# KeyInput_ABH.net
KiCad netlist of a schematic drawn in Altium Designer
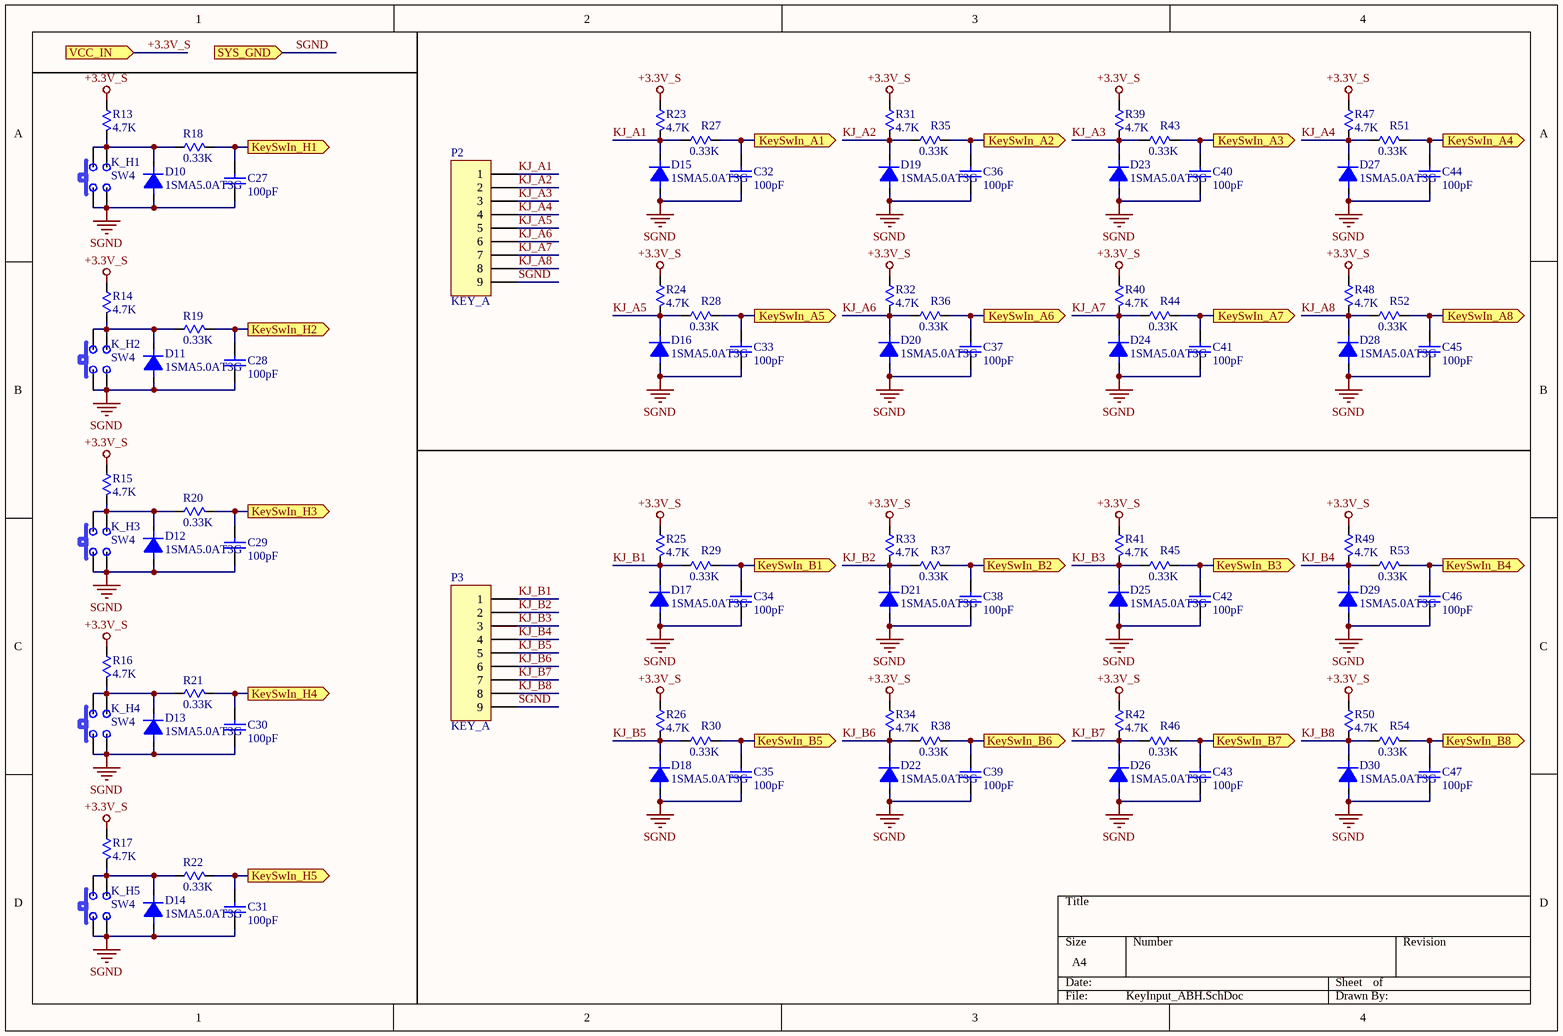
[diagram p0: KeyInput_ABH.SchDoc]

(export (version "E")
  (design (tool "Eeschema 10.0.6"))
  (components
    (comp (ref "C27")
      (value "100pF")
      (footprint "C0805")
      (description "Capacitor")
      (fields (field (name "PUBLISHER") "Altium Limited"))
      (libsource (lib "Miscellaneous Devices") (part "Cap"))
    )
    (comp (ref "C28")
      (value "100pF")
      (footprint "C0805")
      (description "Capacitor")
      (fields (field (name "PUBLISHER") "Altium Limited"))
      (libsource (lib "Miscellaneous Devices") (part "Cap"))
    )
    (comp (ref "C29")
      (value "100pF")
      (footprint "C0805")
      (description "Capacitor")
      (fields (field (name "PUBLISHER") "Altium Limited"))
      (libsource (lib "Miscellaneous Devices") (part "Cap"))
    )
    (comp (ref "C30")
      (value "100pF")
      (footprint "C0805")
      (description "Capacitor")
      (fields (field (name "PUBLISHER") "Altium Limited"))
      (libsource (lib "Miscellaneous Devices") (part "Cap"))
    )
    (comp (ref "C31")
      (value "100pF")
      (footprint "C0805")
      (description "Capacitor")
      (fields (field (name "PUBLISHER") "Altium Limited"))
      (libsource (lib "Miscellaneous Devices") (part "Cap"))
    )
    (comp (ref "C32")
      (value "100pF")
      (footprint "C0805")
      (description "Capacitor")
      (fields (field (name "PUBLISHER") "Altium Limited"))
      (libsource (lib "Miscellaneous Devices") (part "Cap"))
    )
    (comp (ref "C33")
      (value "100pF")
      (footprint "C0805")
      (description "Capacitor")
      (fields (field (name "PUBLISHER") "Altium Limited"))
      (libsource (lib "Miscellaneous Devices") (part "Cap"))
    )
    (comp (ref "C34")
      (value "100pF")
      (footprint "C0805")
      (description "Capacitor")
      (fields (field (name "PUBLISHER") "Altium Limited"))
      (libsource (lib "Miscellaneous Devices") (part "Cap"))
    )
    (comp (ref "C35")
      (value "100pF")
      (footprint "C0805")
      (description "Capacitor")
      (fields (field (name "PUBLISHER") "Altium Limited"))
      (libsource (lib "Miscellaneous Devices") (part "Cap"))
    )
    (comp (ref "C36")
      (value "100pF")
      (footprint "C0805")
      (description "Capacitor")
      (fields (field (name "PUBLISHER") "Altium Limited"))
      (libsource (lib "Miscellaneous Devices") (part "Cap"))
    )
    (comp (ref "C37")
      (value "100pF")
      (footprint "C0805")
      (description "Capacitor")
      (fields (field (name "PUBLISHER") "Altium Limited"))
      (libsource (lib "Miscellaneous Devices") (part "Cap"))
    )
    (comp (ref "C38")
      (value "100pF")
      (footprint "C0805")
      (description "Capacitor")
      (fields (field (name "PUBLISHER") "Altium Limited"))
      (libsource (lib "Miscellaneous Devices") (part "Cap"))
    )
    (comp (ref "C39")
      (value "100pF")
      (footprint "C0805")
      (description "Capacitor")
      (fields (field (name "PUBLISHER") "Altium Limited"))
      (libsource (lib "Miscellaneous Devices") (part "Cap"))
    )
    (comp (ref "C40")
      (value "100pF")
      (footprint "C0805")
      (description "Capacitor")
      (fields (field (name "PUBLISHER") "Altium Limited"))
      (libsource (lib "Miscellaneous Devices") (part "Cap"))
    )
    (comp (ref "C41")
      (value "100pF")
      (footprint "C0805")
      (description "Capacitor")
      (fields (field (name "PUBLISHER") "Altium Limited"))
      (libsource (lib "Miscellaneous Devices") (part "Cap"))
    )
    (comp (ref "C42")
      (value "100pF")
      (footprint "C0805")
      (description "Capacitor")
      (fields (field (name "PUBLISHER") "Altium Limited"))
      (libsource (lib "Miscellaneous Devices") (part "Cap"))
    )
    (comp (ref "C43")
      (value "100pF")
      (footprint "C0805")
      (description "Capacitor")
      (fields (field (name "PUBLISHER") "Altium Limited"))
      (libsource (lib "Miscellaneous Devices") (part "Cap"))
    )
    (comp (ref "C44")
      (value "100pF")
      (footprint "C0805")
      (description "Capacitor")
      (fields (field (name "PUBLISHER") "Altium Limited"))
      (libsource (lib "Miscellaneous Devices") (part "Cap"))
    )
    (comp (ref "C45")
      (value "100pF")
      (footprint "C0805")
      (description "Capacitor")
      (fields (field (name "PUBLISHER") "Altium Limited"))
      (libsource (lib "Miscellaneous Devices") (part "Cap"))
    )
    (comp (ref "C46")
      (value "100pF")
      (footprint "C0805")
      (description "Capacitor")
      (fields (field (name "PUBLISHER") "Altium Limited"))
      (libsource (lib "Miscellaneous Devices") (part "Cap"))
    )
    (comp (ref "C47")
      (value "100pF")
      (footprint "C0805")
      (description "Capacitor")
      (fields (field (name "PUBLISHER") "Altium Limited"))
      (libsource (lib "Miscellaneous Devices") (part "Cap"))
    )
    (comp (ref "D10")
      (value "1SMA5.0AT3G")
      (footprint "SMA")
      (description "Diode")
      (libsource (lib "*") (part "DIODE1"))
    )
    (comp (ref "D11")
      (value "1SMA5.0AT3G")
      (footprint "SMA")
      (description "Diode")
      (libsource (lib "*") (part "DIODE1"))
    )
    (comp (ref "D12")
      (value "1SMA5.0AT3G")
      (footprint "SMA")
      (description "Diode")
      (libsource (lib "*") (part "DIODE1"))
    )
    (comp (ref "D13")
      (value "1SMA5.0AT3G")
      (footprint "SMA")
      (description "Diode")
      (libsource (lib "*") (part "DIODE1"))
    )
    (comp (ref "D14")
      (value "1SMA5.0AT3G")
      (footprint "SMA")
      (description "Diode")
      (libsource (lib "*") (part "DIODE1"))
    )
    (comp (ref "D15")
      (value "1SMA5.0AT3G")
      (footprint "SMA")
      (description "Diode")
      (libsource (lib "*") (part "DIODE1"))
    )
    (comp (ref "D16")
      (value "1SMA5.0AT3G")
      (footprint "SMA")
      (description "Diode")
      (libsource (lib "*") (part "DIODE1"))
    )
    (comp (ref "D17")
      (value "1SMA5.0AT3G")
      (footprint "SMA")
      (description "Diode")
      (libsource (lib "*") (part "DIODE1"))
    )
    (comp (ref "D18")
      (value "1SMA5.0AT3G")
      (footprint "SMA")
      (description "Diode")
      (libsource (lib "*") (part "DIODE1"))
    )
    (comp (ref "D19")
      (value "1SMA5.0AT3G")
      (footprint "SMA")
      (description "Diode")
      (libsource (lib "*") (part "DIODE1"))
    )
    (comp (ref "D20")
      (value "1SMA5.0AT3G")
      (footprint "SMA")
      (description "Diode")
      (libsource (lib "*") (part "DIODE1"))
    )
    (comp (ref "D21")
      (value "1SMA5.0AT3G")
      (footprint "SMA")
      (description "Diode")
      (libsource (lib "*") (part "DIODE1"))
    )
    (comp (ref "D22")
      (value "1SMA5.0AT3G")
      (footprint "SMA")
      (description "Diode")
      (libsource (lib "*") (part "DIODE1"))
    )
    (comp (ref "D23")
      (value "1SMA5.0AT3G")
      (footprint "SMA")
      (description "Diode")
      (libsource (lib "*") (part "DIODE1"))
    )
    (comp (ref "D24")
      (value "1SMA5.0AT3G")
      (footprint "SMA")
      (description "Diode")
      (libsource (lib "*") (part "DIODE1"))
    )
    (comp (ref "D25")
      (value "1SMA5.0AT3G")
      (footprint "SMA")
      (description "Diode")
      (libsource (lib "*") (part "DIODE1"))
    )
    (comp (ref "D26")
      (value "1SMA5.0AT3G")
      (footprint "SMA")
      (description "Diode")
      (libsource (lib "*") (part "DIODE1"))
    )
    (comp (ref "D27")
      (value "1SMA5.0AT3G")
      (footprint "SMA")
      (description "Diode")
      (libsource (lib "*") (part "DIODE1"))
    )
    (comp (ref "D28")
      (value "1SMA5.0AT3G")
      (footprint "SMA")
      (description "Diode")
      (libsource (lib "*") (part "DIODE1"))
    )
    (comp (ref "D29")
      (value "1SMA5.0AT3G")
      (footprint "SMA")
      (description "Diode")
      (libsource (lib "*") (part "DIODE1"))
    )
    (comp (ref "D30")
      (value "1SMA5.0AT3G")
      (footprint "SMA")
      (description "Diode")
      (libsource (lib "*") (part "DIODE1"))
    )
    (comp (ref "K_H1")
      (value "SW4")
      (footprint "SW-MEC")
      (libsource (lib "Passive Components Class") (part "SW-key"))
    )
    (comp (ref "K_H2")
      (value "SW4")
      (footprint "SW-MEC")
      (libsource (lib "Passive Components Class") (part "SW-key"))
    )
    (comp (ref "K_H3")
      (value "SW4")
      (footprint "SW-MEC")
      (libsource (lib "Passive Components Class") (part "SW-key"))
    )
    (comp (ref "K_H4")
      (value "SW4")
      (footprint "SW-MEC")
      (libsource (lib "Passive Components Class") (part "SW-key"))
    )
    (comp (ref "K_H5")
      (value "SW4")
      (footprint "SW-MEC")
      (libsource (lib "Passive Components Class") (part "SW-key"))
    )
    (comp (ref "P2")
      (value "KEY_A")
      (footprint "HDR1X9")
      (description "Header, 9-Pin")
      (fields (field (name "PUBLISHER") "Altium Limited"))
      (libsource (lib "Miscellaneous Connectors") (part "Header 9"))
    )
    (comp (ref "P3")
      (value "KEY_A")
      (footprint "HDR1X9")
      (description "Header, 9-Pin")
      (fields (field (name "PUBLISHER") "Altium Limited"))
      (libsource (lib "Miscellaneous Connectors") (part "Header 9"))
    )
    (comp (ref "R13")
      (value "4.7K")
      (footprint "R0805")
      (description "Resistor")
      (fields (field (name "PUBLISHER") "Altium Limited"))
      (libsource (lib "Passive Components Class") (part "RES"))
    )
    (comp (ref "R14")
      (value "4.7K")
      (footprint "R0805")
      (description "Resistor")
      (fields (field (name "PUBLISHER") "Altium Limited"))
      (libsource (lib "Passive Components Class") (part "RES"))
    )
    (comp (ref "R15")
      (value "4.7K")
      (footprint "R0805")
      (description "Resistor")
      (fields (field (name "PUBLISHER") "Altium Limited"))
      (libsource (lib "Passive Components Class") (part "RES"))
    )
    (comp (ref "R16")
      (value "4.7K")
      (footprint "R0805")
      (description "Resistor")
      (fields (field (name "PUBLISHER") "Altium Limited"))
      (libsource (lib "Passive Components Class") (part "RES"))
    )
    (comp (ref "R17")
      (value "4.7K")
      (footprint "R0805")
      (description "Resistor")
      (fields (field (name "PUBLISHER") "Altium Limited"))
      (libsource (lib "Passive Components Class") (part "RES"))
    )
    (comp (ref "R18")
      (value "0.33K")
      (footprint "R0805")
      (description "Resistor")
      (fields (field (name "PUBLISHER") "Altium Limited"))
      (libsource (lib "Passive Components Class") (part "RES"))
    )
    (comp (ref "R19")
      (value "0.33K")
      (footprint "R0805")
      (description "Resistor")
      (fields (field (name "PUBLISHER") "Altium Limited"))
      (libsource (lib "Passive Components Class") (part "RES"))
    )
    (comp (ref "R20")
      (value "0.33K")
      (footprint "R0805")
      (description "Resistor")
      (fields (field (name "PUBLISHER") "Altium Limited"))
      (libsource (lib "Passive Components Class") (part "RES"))
    )
    (comp (ref "R21")
      (value "0.33K")
      (footprint "R0805")
      (description "Resistor")
      (fields (field (name "PUBLISHER") "Altium Limited"))
      (libsource (lib "Passive Components Class") (part "RES"))
    )
    (comp (ref "R22")
      (value "0.33K")
      (footprint "R0805")
      (description "Resistor")
      (fields (field (name "PUBLISHER") "Altium Limited"))
      (libsource (lib "Passive Components Class") (part "RES"))
    )
    (comp (ref "R23")
      (value "4.7K")
      (footprint "R0805")
      (description "Resistor")
      (fields (field (name "PUBLISHER") "Altium Limited"))
      (libsource (lib "Passive Components Class") (part "RES"))
    )
    (comp (ref "R24")
      (value "4.7K")
      (footprint "R0805")
      (description "Resistor")
      (fields (field (name "PUBLISHER") "Altium Limited"))
      (libsource (lib "Passive Components Class") (part "RES"))
    )
    (comp (ref "R25")
      (value "4.7K")
      (footprint "R0805")
      (description "Resistor")
      (fields (field (name "PUBLISHER") "Altium Limited"))
      (libsource (lib "Passive Components Class") (part "RES"))
    )
    (comp (ref "R26")
      (value "4.7K")
      (footprint "R0805")
      (description "Resistor")
      (fields (field (name "PUBLISHER") "Altium Limited"))
      (libsource (lib "Passive Components Class") (part "RES"))
    )
    (comp (ref "R27")
      (value "0.33K")
      (footprint "R0805")
      (description "Resistor")
      (fields (field (name "PUBLISHER") "Altium Limited"))
      (libsource (lib "Passive Components Class") (part "RES"))
    )
    (comp (ref "R28")
      (value "0.33K")
      (footprint "R0805")
      (description "Resistor")
      (fields (field (name "PUBLISHER") "Altium Limited"))
      (libsource (lib "Passive Components Class") (part "RES"))
    )
    (comp (ref "R29")
      (value "0.33K")
      (footprint "R0805")
      (description "Resistor")
      (fields (field (name "PUBLISHER") "Altium Limited"))
      (libsource (lib "Passive Components Class") (part "RES"))
    )
    (comp (ref "R30")
      (value "0.33K")
      (footprint "R0805")
      (description "Resistor")
      (fields (field (name "PUBLISHER") "Altium Limited"))
      (libsource (lib "Passive Components Class") (part "RES"))
    )
    (comp (ref "R31")
      (value "4.7K")
      (footprint "R0805")
      (description "Resistor")
      (fields (field (name "PUBLISHER") "Altium Limited"))
      (libsource (lib "Passive Components Class") (part "RES"))
    )
    (comp (ref "R32")
      (value "4.7K")
      (footprint "R0805")
      (description "Resistor")
      (fields (field (name "PUBLISHER") "Altium Limited"))
      (libsource (lib "Passive Components Class") (part "RES"))
    )
    (comp (ref "R33")
      (value "4.7K")
      (footprint "R0805")
      (description "Resistor")
      (fields (field (name "PUBLISHER") "Altium Limited"))
      (libsource (lib "Passive Components Class") (part "RES"))
    )
    (comp (ref "R34")
      (value "4.7K")
      (footprint "R0805")
      (description "Resistor")
      (fields (field (name "PUBLISHER") "Altium Limited"))
      (libsource (lib "Passive Components Class") (part "RES"))
    )
    (comp (ref "R35")
      (value "0.33K")
      (footprint "R0805")
      (description "Resistor")
      (fields (field (name "PUBLISHER") "Altium Limited"))
      (libsource (lib "Passive Components Class") (part "RES"))
    )
    (comp (ref "R36")
      (value "0.33K")
      (footprint "R0805")
      (description "Resistor")
      (fields (field (name "PUBLISHER") "Altium Limited"))
      (libsource (lib "Passive Components Class") (part "RES"))
    )
    (comp (ref "R37")
      (value "0.33K")
      (footprint "R0805")
      (description "Resistor")
      (fields (field (name "PUBLISHER") "Altium Limited"))
      (libsource (lib "Passive Components Class") (part "RES"))
    )
    (comp (ref "R38")
      (value "0.33K")
      (footprint "R0805")
      (description "Resistor")
      (fields (field (name "PUBLISHER") "Altium Limited"))
      (libsource (lib "Passive Components Class") (part "RES"))
    )
    (comp (ref "R39")
      (value "4.7K")
      (footprint "R0805")
      (description "Resistor")
      (fields (field (name "PUBLISHER") "Altium Limited"))
      (libsource (lib "Passive Components Class") (part "RES"))
    )
    (comp (ref "R40")
      (value "4.7K")
      (footprint "R0805")
      (description "Resistor")
      (fields (field (name "PUBLISHER") "Altium Limited"))
      (libsource (lib "Passive Components Class") (part "RES"))
    )
    (comp (ref "R41")
      (value "4.7K")
      (footprint "R0805")
      (description "Resistor")
      (fields (field (name "PUBLISHER") "Altium Limited"))
      (libsource (lib "Passive Components Class") (part "RES"))
    )
    (comp (ref "R42")
      (value "4.7K")
      (footprint "R0805")
      (description "Resistor")
      (fields (field (name "PUBLISHER") "Altium Limited"))
      (libsource (lib "Passive Components Class") (part "RES"))
    )
    (comp (ref "R43")
      (value "0.33K")
      (footprint "R0805")
      (description "Resistor")
      (fields (field (name "PUBLISHER") "Altium Limited"))
      (libsource (lib "Passive Components Class") (part "RES"))
    )
    (comp (ref "R44")
      (value "0.33K")
      (footprint "R0805")
      (description "Resistor")
      (fields (field (name "PUBLISHER") "Altium Limited"))
      (libsource (lib "Passive Components Class") (part "RES"))
    )
    (comp (ref "R45")
      (value "0.33K")
      (footprint "R0805")
      (description "Resistor")
      (fields (field (name "PUBLISHER") "Altium Limited"))
      (libsource (lib "Passive Components Class") (part "RES"))
    )
    (comp (ref "R46")
      (value "0.33K")
      (footprint "R0805")
      (description "Resistor")
      (fields (field (name "PUBLISHER") "Altium Limited"))
      (libsource (lib "Passive Components Class") (part "RES"))
    )
    (comp (ref "R47")
      (value "4.7K")
      (footprint "R0805")
      (description "Resistor")
      (fields (field (name "PUBLISHER") "Altium Limited"))
      (libsource (lib "Passive Components Class") (part "RES"))
    )
    (comp (ref "R48")
      (value "4.7K")
      (footprint "R0805")
      (description "Resistor")
      (fields (field (name "PUBLISHER") "Altium Limited"))
      (libsource (lib "Passive Components Class") (part "RES"))
    )
    (comp (ref "R49")
      (value "4.7K")
      (footprint "R0805")
      (description "Resistor")
      (fields (field (name "PUBLISHER") "Altium Limited"))
      (libsource (lib "Passive Components Class") (part "RES"))
    )
    (comp (ref "R50")
      (value "4.7K")
      (footprint "R0805")
      (description "Resistor")
      (fields (field (name "PUBLISHER") "Altium Limited"))
      (libsource (lib "Passive Components Class") (part "RES"))
    )
    (comp (ref "R51")
      (value "0.33K")
      (footprint "R0805")
      (description "Resistor")
      (fields (field (name "PUBLISHER") "Altium Limited"))
      (libsource (lib "Passive Components Class") (part "RES"))
    )
    (comp (ref "R52")
      (value "0.33K")
      (footprint "R0805")
      (description "Resistor")
      (fields (field (name "PUBLISHER") "Altium Limited"))
      (libsource (lib "Passive Components Class") (part "RES"))
    )
    (comp (ref "R53")
      (value "0.33K")
      (footprint "R0805")
      (description "Resistor")
      (fields (field (name "PUBLISHER") "Altium Limited"))
      (libsource (lib "Passive Components Class") (part "RES"))
    )
    (comp (ref "R54")
      (value "0.33K")
      (footprint "R0805")
      (description "Resistor")
      (fields (field (name "PUBLISHER") "Altium Limited"))
      (libsource (lib "Passive Components Class") (part "RES"))
    )
  )
  (nets
    (net (code "1") (name "+3.3V_S") (class "Default")
      (node (ref "R13") (pin "2") (pinfunction "2_2") (pintype "passive"))
      (node (ref "R14") (pin "2") (pinfunction "2_2") (pintype "passive"))
      (node (ref "R15") (pin "2") (pinfunction "2_2") (pintype "passive"))
      (node (ref "R16") (pin "2") (pinfunction "2_2") (pintype "passive"))
      (node (ref "R17") (pin "2") (pinfunction "2_2") (pintype "passive"))
      (node (ref "R23") (pin "2") (pinfunction "2_2") (pintype "passive"))
      (node (ref "R24") (pin "2") (pinfunction "2_2") (pintype "passive"))
      (node (ref "R25") (pin "2") (pinfunction "2_2") (pintype "passive"))
      (node (ref "R26") (pin "2") (pinfunction "2_2") (pintype "passive"))
      (node (ref "R31") (pin "2") (pinfunction "2_2") (pintype "passive"))
      (node (ref "R32") (pin "2") (pinfunction "2_2") (pintype "passive"))
      (node (ref "R33") (pin "2") (pinfunction "2_2") (pintype "passive"))
      (node (ref "R34") (pin "2") (pinfunction "2_2") (pintype "passive"))
      (node (ref "R39") (pin "2") (pinfunction "2_2") (pintype "passive"))
      (node (ref "R40") (pin "2") (pinfunction "2_2") (pintype "passive"))
      (node (ref "R41") (pin "2") (pinfunction "2_2") (pintype "passive"))
      (node (ref "R42") (pin "2") (pinfunction "2_2") (pintype "passive"))
      (node (ref "R47") (pin "2") (pinfunction "2_2") (pintype "passive"))
      (node (ref "R48") (pin "2") (pinfunction "2_2") (pintype "passive"))
      (node (ref "R49") (pin "2") (pinfunction "2_2") (pintype "passive"))
      (node (ref "R50") (pin "2") (pinfunction "2_2") (pintype "passive"))
    )
    (net (code "2") (name "/KJ_A1") (class "Default")
      (node (ref "D15") (pin "2") (pinfunction "K_2") (pintype "passive"))
      (node (ref "P2") (pin "1") (pinfunction "1_1") (pintype "passive"))
      (node (ref "R23") (pin "1") (pinfunction "1_1") (pintype "passive"))
      (node (ref "R27") (pin "2") (pinfunction "2_2") (pintype "passive"))
    )
    (net (code "3") (name "/KJ_A2") (class "Default")
      (node (ref "D19") (pin "2") (pinfunction "K_2") (pintype "passive"))
      (node (ref "P2") (pin "2") (pinfunction "2_2") (pintype "passive"))
      (node (ref "R31") (pin "1") (pinfunction "1_1") (pintype "passive"))
      (node (ref "R35") (pin "2") (pinfunction "2_2") (pintype "passive"))
    )
    (net (code "4") (name "/KJ_A3") (class "Default")
      (node (ref "D23") (pin "2") (pinfunction "K_2") (pintype "passive"))
      (node (ref "P2") (pin "3") (pinfunction "3_3") (pintype "passive"))
      (node (ref "R39") (pin "1") (pinfunction "1_1") (pintype "passive"))
      (node (ref "R43") (pin "2") (pinfunction "2_2") (pintype "passive"))
    )
    (net (code "5") (name "/KJ_A4") (class "Default")
      (node (ref "D27") (pin "2") (pinfunction "K_2") (pintype "passive"))
      (node (ref "P2") (pin "4") (pinfunction "4_4") (pintype "passive"))
      (node (ref "R47") (pin "1") (pinfunction "1_1") (pintype "passive"))
      (node (ref "R51") (pin "2") (pinfunction "2_2") (pintype "passive"))
    )
    (net (code "6") (name "/KJ_A5") (class "Default")
      (node (ref "D16") (pin "2") (pinfunction "K_2") (pintype "passive"))
      (node (ref "P2") (pin "5") (pinfunction "5_5") (pintype "passive"))
      (node (ref "R24") (pin "1") (pinfunction "1_1") (pintype "passive"))
      (node (ref "R28") (pin "2") (pinfunction "2_2") (pintype "passive"))
    )
    (net (code "7") (name "/KJ_A6") (class "Default")
      (node (ref "D20") (pin "2") (pinfunction "K_2") (pintype "passive"))
      (node (ref "P2") (pin "6") (pinfunction "6_6") (pintype "passive"))
      (node (ref "R32") (pin "1") (pinfunction "1_1") (pintype "passive"))
      (node (ref "R36") (pin "2") (pinfunction "2_2") (pintype "passive"))
    )
    (net (code "8") (name "/KJ_A7") (class "Default")
      (node (ref "D24") (pin "2") (pinfunction "K_2") (pintype "passive"))
      (node (ref "P2") (pin "7") (pinfunction "7_7") (pintype "passive"))
      (node (ref "R40") (pin "1") (pinfunction "1_1") (pintype "passive"))
      (node (ref "R44") (pin "2") (pinfunction "2_2") (pintype "passive"))
    )
    (net (code "9") (name "/KJ_A8") (class "Default")
      (node (ref "D28") (pin "2") (pinfunction "K_2") (pintype "passive"))
      (node (ref "P2") (pin "8") (pinfunction "8_8") (pintype "passive"))
      (node (ref "R48") (pin "1") (pinfunction "1_1") (pintype "passive"))
      (node (ref "R52") (pin "2") (pinfunction "2_2") (pintype "passive"))
    )
    (net (code "10") (name "/KJ_B1") (class "Default")
      (node (ref "D17") (pin "2") (pinfunction "K_2") (pintype "passive"))
      (node (ref "P3") (pin "1") (pinfunction "1_1") (pintype "passive"))
      (node (ref "R25") (pin "1") (pinfunction "1_1") (pintype "passive"))
      (node (ref "R29") (pin "2") (pinfunction "2_2") (pintype "passive"))
    )
    (net (code "11") (name "/KJ_B2") (class "Default")
      (node (ref "D21") (pin "2") (pinfunction "K_2") (pintype "passive"))
      (node (ref "P3") (pin "2") (pinfunction "2_2") (pintype "passive"))
      (node (ref "R33") (pin "1") (pinfunction "1_1") (pintype "passive"))
      (node (ref "R37") (pin "2") (pinfunction "2_2") (pintype "passive"))
    )
    (net (code "12") (name "/KJ_B3") (class "Default")
      (node (ref "D25") (pin "2") (pinfunction "K_2") (pintype "passive"))
      (node (ref "P3") (pin "3") (pinfunction "3_3") (pintype "passive"))
      (node (ref "R41") (pin "1") (pinfunction "1_1") (pintype "passive"))
      (node (ref "R45") (pin "2") (pinfunction "2_2") (pintype "passive"))
    )
    (net (code "13") (name "/KJ_B4") (class "Default")
      (node (ref "D29") (pin "2") (pinfunction "K_2") (pintype "passive"))
      (node (ref "P3") (pin "4") (pinfunction "4_4") (pintype "passive"))
      (node (ref "R49") (pin "1") (pinfunction "1_1") (pintype "passive"))
      (node (ref "R53") (pin "2") (pinfunction "2_2") (pintype "passive"))
    )
    (net (code "14") (name "/KJ_B5") (class "Default")
      (node (ref "D18") (pin "2") (pinfunction "K_2") (pintype "passive"))
      (node (ref "P3") (pin "5") (pinfunction "5_5") (pintype "passive"))
      (node (ref "R26") (pin "1") (pinfunction "1_1") (pintype "passive"))
      (node (ref "R30") (pin "2") (pinfunction "2_2") (pintype "passive"))
    )
    (net (code "15") (name "/KJ_B6") (class "Default")
      (node (ref "D22") (pin "2") (pinfunction "K_2") (pintype "passive"))
      (node (ref "P3") (pin "6") (pinfunction "6_6") (pintype "passive"))
      (node (ref "R34") (pin "1") (pinfunction "1_1") (pintype "passive"))
      (node (ref "R38") (pin "2") (pinfunction "2_2") (pintype "passive"))
    )
    (net (code "16") (name "/KJ_B7") (class "Default")
      (node (ref "D26") (pin "2") (pinfunction "K_2") (pintype "passive"))
      (node (ref "P3") (pin "7") (pinfunction "7_7") (pintype "passive"))
      (node (ref "R42") (pin "1") (pinfunction "1_1") (pintype "passive"))
      (node (ref "R46") (pin "2") (pinfunction "2_2") (pintype "passive"))
    )
    (net (code "17") (name "/KJ_B8") (class "Default")
      (node (ref "D30") (pin "2") (pinfunction "K_2") (pintype "passive"))
      (node (ref "P3") (pin "8") (pinfunction "8_8") (pintype "passive"))
      (node (ref "R50") (pin "1") (pinfunction "1_1") (pintype "passive"))
      (node (ref "R54") (pin "2") (pinfunction "2_2") (pintype "passive"))
    )
    (net (code "18") (name "/KeySwIn_A1") (class "Default")
      (node (ref "C32") (pin "1") (pinfunction "1_1") (pintype "passive"))
      (node (ref "R27") (pin "1") (pinfunction "1_1") (pintype "passive"))
    )
    (net (code "19") (name "/KeySwIn_A2") (class "Default")
      (node (ref "C36") (pin "1") (pinfunction "1_1") (pintype "passive"))
      (node (ref "R35") (pin "1") (pinfunction "1_1") (pintype "passive"))
    )
    (net (code "20") (name "/KeySwIn_A3") (class "Default")
      (node (ref "C40") (pin "1") (pinfunction "1_1") (pintype "passive"))
      (node (ref "R43") (pin "1") (pinfunction "1_1") (pintype "passive"))
    )
    (net (code "21") (name "/KeySwIn_A4") (class "Default")
      (node (ref "C44") (pin "1") (pinfunction "1_1") (pintype "passive"))
      (node (ref "R51") (pin "1") (pinfunction "1_1") (pintype "passive"))
    )
    (net (code "22") (name "/KeySwIn_A5") (class "Default")
      (node (ref "C33") (pin "1") (pinfunction "1_1") (pintype "passive"))
      (node (ref "R28") (pin "1") (pinfunction "1_1") (pintype "passive"))
    )
    (net (code "23") (name "/KeySwIn_A6") (class "Default")
      (node (ref "C37") (pin "1") (pinfunction "1_1") (pintype "passive"))
      (node (ref "R36") (pin "1") (pinfunction "1_1") (pintype "passive"))
    )
    (net (code "24") (name "/KeySwIn_A7") (class "Default")
      (node (ref "C41") (pin "1") (pinfunction "1_1") (pintype "passive"))
      (node (ref "R44") (pin "1") (pinfunction "1_1") (pintype "passive"))
    )
    (net (code "25") (name "/KeySwIn_A8") (class "Default")
      (node (ref "C45") (pin "1") (pinfunction "1_1") (pintype "passive"))
      (node (ref "R52") (pin "1") (pinfunction "1_1") (pintype "passive"))
    )
    (net (code "26") (name "/KeySwIn_B1") (class "Default")
      (node (ref "C34") (pin "1") (pinfunction "1_1") (pintype "passive"))
      (node (ref "R29") (pin "1") (pinfunction "1_1") (pintype "passive"))
    )
    (net (code "27") (name "/KeySwIn_B2") (class "Default")
      (node (ref "C38") (pin "1") (pinfunction "1_1") (pintype "passive"))
      (node (ref "R37") (pin "1") (pinfunction "1_1") (pintype "passive"))
    )
    (net (code "28") (name "/KeySwIn_B3") (class "Default")
      (node (ref "C42") (pin "1") (pinfunction "1_1") (pintype "passive"))
      (node (ref "R45") (pin "1") (pinfunction "1_1") (pintype "passive"))
    )
    (net (code "29") (name "/KeySwIn_B4") (class "Default")
      (node (ref "C46") (pin "1") (pinfunction "1_1") (pintype "passive"))
      (node (ref "R53") (pin "1") (pinfunction "1_1") (pintype "passive"))
    )
    (net (code "30") (name "/KeySwIn_B5") (class "Default")
      (node (ref "C35") (pin "1") (pinfunction "1_1") (pintype "passive"))
      (node (ref "R30") (pin "1") (pinfunction "1_1") (pintype "passive"))
    )
    (net (code "31") (name "/KeySwIn_B6") (class "Default")
      (node (ref "C39") (pin "1") (pinfunction "1_1") (pintype "passive"))
      (node (ref "R38") (pin "1") (pinfunction "1_1") (pintype "passive"))
    )
    (net (code "32") (name "/KeySwIn_B7") (class "Default")
      (node (ref "C43") (pin "1") (pinfunction "1_1") (pintype "passive"))
      (node (ref "R46") (pin "1") (pinfunction "1_1") (pintype "passive"))
    )
    (net (code "33") (name "/KeySwIn_B8") (class "Default")
      (node (ref "C47") (pin "1") (pinfunction "1_1") (pintype "passive"))
      (node (ref "R54") (pin "1") (pinfunction "1_1") (pintype "passive"))
    )
    (net (code "34") (name "/KeySwIn_H1") (class "Default")
      (node (ref "C27") (pin "1") (pinfunction "1_1") (pintype "passive"))
      (node (ref "R18") (pin "1") (pinfunction "1_1") (pintype "passive"))
    )
    (net (code "35") (name "/KeySwIn_H2") (class "Default")
      (node (ref "C28") (pin "1") (pinfunction "1_1") (pintype "passive"))
      (node (ref "R19") (pin "1") (pinfunction "1_1") (pintype "passive"))
    )
    (net (code "36") (name "/KeySwIn_H3") (class "Default")
      (node (ref "C29") (pin "1") (pinfunction "1_1") (pintype "passive"))
      (node (ref "R20") (pin "1") (pinfunction "1_1") (pintype "passive"))
    )
    (net (code "37") (name "/KeySwIn_H4") (class "Default")
      (node (ref "C30") (pin "1") (pinfunction "1_1") (pintype "passive"))
      (node (ref "R21") (pin "1") (pinfunction "1_1") (pintype "passive"))
    )
    (net (code "38") (name "/KeySwIn_H5") (class "Default")
      (node (ref "C31") (pin "1") (pinfunction "1_1") (pintype "passive"))
      (node (ref "R22") (pin "1") (pinfunction "1_1") (pintype "passive"))
    )
    (net (code "39") (name "Net-(D10-K)") (class "Default")
      (node (ref "D10") (pin "2") (pinfunction "K_2") (pintype "passive"))
      (node (ref "K_H1") (pin "2") (pinfunction "2_2") (pintype "passive"))
      (node (ref "R13") (pin "1") (pinfunction "1_1") (pintype "passive"))
      (node (ref "R18") (pin "2") (pinfunction "2_2") (pintype "passive"))
    )
    (net (code "40") (name "Net-(D11-K)") (class "Default")
      (node (ref "D11") (pin "2") (pinfunction "K_2") (pintype "passive"))
      (node (ref "K_H2") (pin "2") (pinfunction "2_2") (pintype "passive"))
      (node (ref "R14") (pin "1") (pinfunction "1_1") (pintype "passive"))
      (node (ref "R19") (pin "2") (pinfunction "2_2") (pintype "passive"))
    )
    (net (code "41") (name "Net-(D12-K)") (class "Default")
      (node (ref "D12") (pin "2") (pinfunction "K_2") (pintype "passive"))
      (node (ref "K_H3") (pin "2") (pinfunction "2_2") (pintype "passive"))
      (node (ref "R15") (pin "1") (pinfunction "1_1") (pintype "passive"))
      (node (ref "R20") (pin "2") (pinfunction "2_2") (pintype "passive"))
    )
    (net (code "42") (name "Net-(D13-K)") (class "Default")
      (node (ref "D13") (pin "2") (pinfunction "K_2") (pintype "passive"))
      (node (ref "K_H4") (pin "2") (pinfunction "2_2") (pintype "passive"))
      (node (ref "R16") (pin "1") (pinfunction "1_1") (pintype "passive"))
      (node (ref "R21") (pin "2") (pinfunction "2_2") (pintype "passive"))
    )
    (net (code "43") (name "Net-(D14-K)") (class "Default")
      (node (ref "D14") (pin "2") (pinfunction "K_2") (pintype "passive"))
      (node (ref "K_H5") (pin "2") (pinfunction "2_2") (pintype "passive"))
      (node (ref "R17") (pin "1") (pinfunction "1_1") (pintype "passive"))
      (node (ref "R22") (pin "2") (pinfunction "2_2") (pintype "passive"))
    )
    (net (code "44") (name "SGND") (class "Default")
      (node (ref "C27") (pin "2") (pinfunction "2_2") (pintype "passive"))
      (node (ref "C28") (pin "2") (pinfunction "2_2") (pintype "passive"))
      (node (ref "C29") (pin "2") (pinfunction "2_2") (pintype "passive"))
      (node (ref "C30") (pin "2") (pinfunction "2_2") (pintype "passive"))
      (node (ref "C31") (pin "2") (pinfunction "2_2") (pintype "passive"))
      (node (ref "C32") (pin "2") (pinfunction "2_2") (pintype "passive"))
      (node (ref "C33") (pin "2") (pinfunction "2_2") (pintype "passive"))
      (node (ref "C34") (pin "2") (pinfunction "2_2") (pintype "passive"))
      (node (ref "C35") (pin "2") (pinfunction "2_2") (pintype "passive"))
      (node (ref "C36") (pin "2") (pinfunction "2_2") (pintype "passive"))
      (node (ref "C37") (pin "2") (pinfunction "2_2") (pintype "passive"))
      (node (ref "C38") (pin "2") (pinfunction "2_2") (pintype "passive"))
      (node (ref "C39") (pin "2") (pinfunction "2_2") (pintype "passive"))
      (node (ref "C40") (pin "2") (pinfunction "2_2") (pintype "passive"))
      (node (ref "C41") (pin "2") (pinfunction "2_2") (pintype "passive"))
      (node (ref "C42") (pin "2") (pinfunction "2_2") (pintype "passive"))
      (node (ref "C43") (pin "2") (pinfunction "2_2") (pintype "passive"))
      (node (ref "C44") (pin "2") (pinfunction "2_2") (pintype "passive"))
      (node (ref "C45") (pin "2") (pinfunction "2_2") (pintype "passive"))
      (node (ref "C46") (pin "2") (pinfunction "2_2") (pintype "passive"))
      (node (ref "C47") (pin "2") (pinfunction "2_2") (pintype "passive"))
      (node (ref "D10") (pin "1") (pinfunction "A_1") (pintype "passive"))
      (node (ref "D11") (pin "1") (pinfunction "A_1") (pintype "passive"))
      (node (ref "D12") (pin "1") (pinfunction "A_1") (pintype "passive"))
      (node (ref "D13") (pin "1") (pinfunction "A_1") (pintype "passive"))
      (node (ref "D14") (pin "1") (pinfunction "A_1") (pintype "passive"))
      (node (ref "D15") (pin "1") (pinfunction "A_1") (pintype "passive"))
      (node (ref "D16") (pin "1") (pinfunction "A_1") (pintype "passive"))
      (node (ref "D17") (pin "1") (pinfunction "A_1") (pintype "passive"))
      (node (ref "D18") (pin "1") (pinfunction "A_1") (pintype "passive"))
      (node (ref "D19") (pin "1") (pinfunction "A_1") (pintype "passive"))
      (node (ref "D20") (pin "1") (pinfunction "A_1") (pintype "passive"))
      (node (ref "D21") (pin "1") (pinfunction "A_1") (pintype "passive"))
      (node (ref "D22") (pin "1") (pinfunction "A_1") (pintype "passive"))
      (node (ref "D23") (pin "1") (pinfunction "A_1") (pintype "passive"))
      (node (ref "D24") (pin "1") (pinfunction "A_1") (pintype "passive"))
      (node (ref "D25") (pin "1") (pinfunction "A_1") (pintype "passive"))
      (node (ref "D26") (pin "1") (pinfunction "A_1") (pintype "passive"))
      (node (ref "D27") (pin "1") (pinfunction "A_1") (pintype "passive"))
      (node (ref "D28") (pin "1") (pinfunction "A_1") (pintype "passive"))
      (node (ref "D29") (pin "1") (pinfunction "A_1") (pintype "passive"))
      (node (ref "D30") (pin "1") (pinfunction "A_1") (pintype "passive"))
      (node (ref "K_H1") (pin "1") (pinfunction "1_1") (pintype "passive"))
      (node (ref "K_H2") (pin "1") (pinfunction "1_1") (pintype "passive"))
      (node (ref "K_H3") (pin "1") (pinfunction "1_1") (pintype "passive"))
      (node (ref "K_H4") (pin "1") (pinfunction "1_1") (pintype "passive"))
      (node (ref "K_H5") (pin "1") (pinfunction "1_1") (pintype "passive"))
      (node (ref "P2") (pin "9") (pinfunction "9_9") (pintype "passive"))
      (node (ref "P3") (pin "9") (pinfunction "9_9") (pintype "passive"))
    )
  )
)
